# Power.net
KiCad netlist of a schematic drawn in Altium Designer
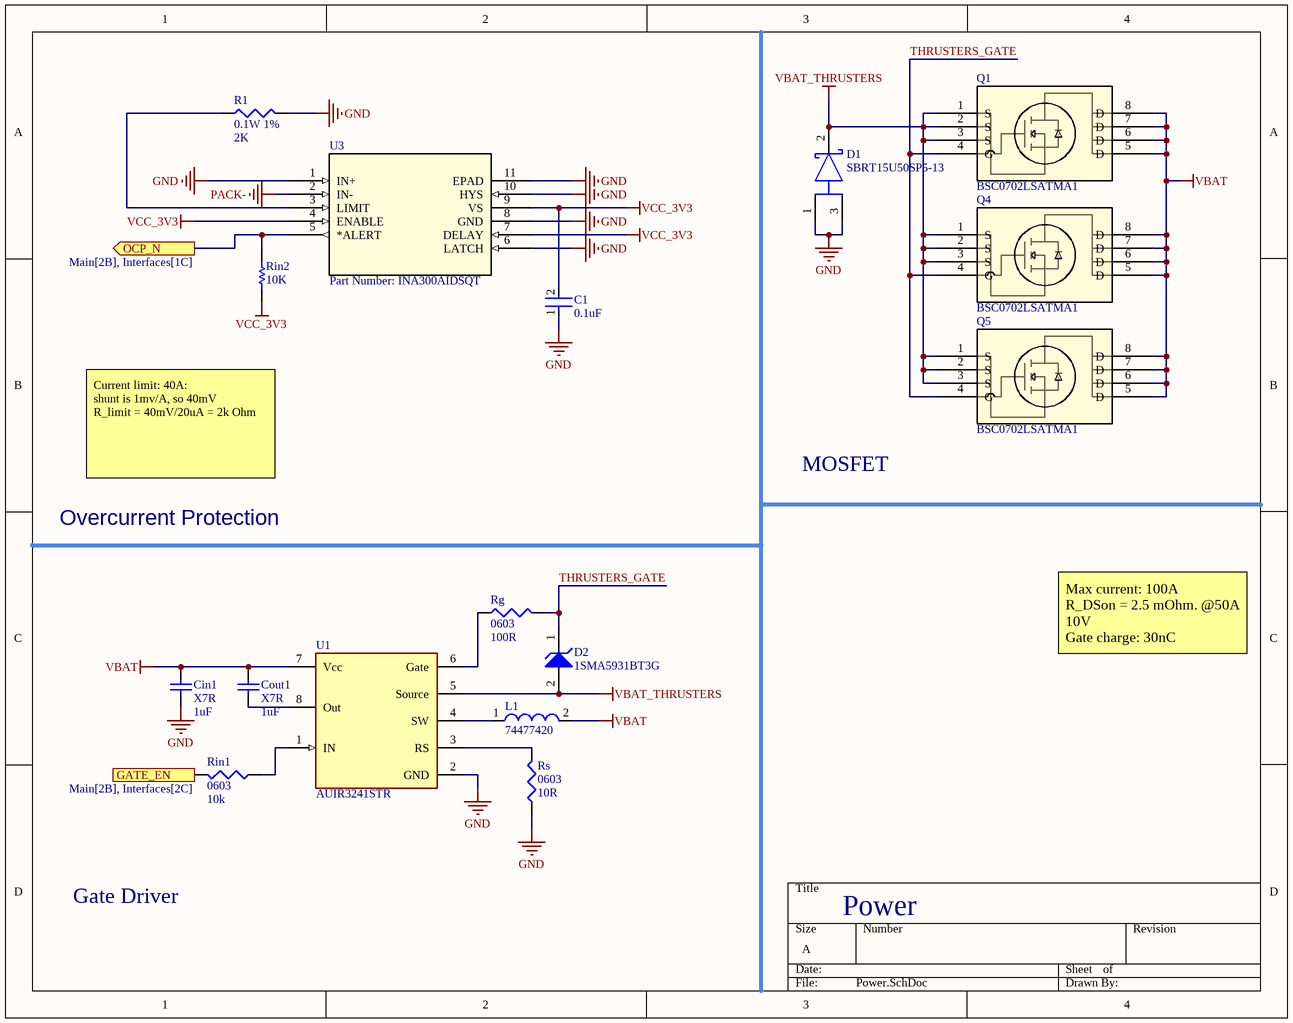
[diagram p0: Power.SchDoc]

(export (version "E")
  (design (tool "Eeschema 10.0.6"))
  (components
    (comp (ref "C1")
      (value "0.1uF")
      (footprint "FP-C0603C-CF-MFG")
      (description "CAP CER 0.1UF 10V X7R 0603")
      (fields (field (name "TOLERANCE") "0.1") (field (name "MANUFACTURER PART NUMBER") "C0603C104K8RACTU"))
      (libsource (lib "Altium Content Vault") (part "b4654b650e69147ec39a6b967a45e02"))
    )
    (comp (ref "Cin1")
      (value "X7R")
      (footprint "C0805")
      (description "Capacitor")
      (fields (field (name "ALTIUM_VALUE") "1uF") (field (name "PUBLISHER") "Altium Limited"))
      (libsource (lib "Miscellaneous Devices") (part "Cap"))
    )
    (comp (ref "Cout1")
      (value "X7R")
      (footprint "C0805")
      (description "Capacitor")
      (fields (field (name "ALTIUM_VALUE") "1uF") (field (name "PUBLISHER") "Altium Limited"))
      (libsource (lib "Miscellaneous Devices") (part "Cap"))
    )
    (comp (ref "D1")
      (value "SBRT15U50SP5-13")
      (footprint "FP-PowerDI5-MFG")
      (description "50V 15A Rectifier Schottky Diode")
      (fields
        (field (name "OCTOPART") "https://octopart.com/pds3200-13-diodes+inc.-332544")
        (field (name "MANUFACTURER") "Diodes Inc.")
      )
      (libsource (lib "Altium Content Vault") (part "0222f6c3f9f8f3c07decc49f824026a"))
    )
    (comp (ref "D2")
      (value "1SMA5931BT3G")
      (footprint "ONSC-SMA-2-403D-02_F_V")
      (description "1.5 W Zener Voltage Regulator, 2-Pin SMA, Pb-Free, Tape and Reel")
      (fields (field (name "MANUFACTURER") "On Semiconductor"))
      (libsource (lib "Altium Content Vault") (part "ONSC-K1A2-2"))
    )
    (comp (ref "L1")
      (value "74477420")
      (footprint "WE-PD2-M")
      (description "SMD Power Inductor WE-PD2, L = 100 µH")
      (libsource (lib "Altium Content Vault") (part "PAS-IND-INDUCTOR-2"))
    )
    (comp (ref "Q1")
      (value "BSC0702LSATMA1")
      (footprint "PG-TDSON-8-7")
      (description "No Description Available")
      (libsource (lib "TAUV-Lib") (part "BSC0702LSATMA1"))
    )
    (comp (ref "Q4")
      (value "BSC0702LSATMA1")
      (footprint "PG-TDSON-8-7")
      (description "No Description Available")
      (libsource (lib "TAUV-Lib") (part "BSC0702LSATMA1"))
    )
    (comp (ref "Q5")
      (value "BSC0702LSATMA1")
      (footprint "PG-TDSON-8-7")
      (description "No Description Available")
      (libsource (lib "TAUV-Lib") (part "BSC0702LSATMA1"))
    )
    (comp (ref "R1")
      (value "0.1W 1%")
      (footprint "J1-0603")
      (description "2k 0.1W 1%")
      (fields (field (name "ALTIUM_VALUE") "2K") (field (name "PUBLISHER") "Altium Limited"))
      (libsource (lib "Miscellaneous Devices") (part "Res3"))
    )
    (comp (ref "Rg")
      (value "0603")
      (footprint "J1-0603")
      (description "Resistor")
      (fields (field (name "ALTIUM_VALUE") "100R") (field (name "PUBLISHER") "Altium Limited"))
      (libsource (lib "Miscellaneous Devices") (part "Res3"))
    )
    (comp (ref "Rin1")
      (value "0603")
      (footprint "J1-0603")
      (description "Resistor")
      (fields (field (name "ALTIUM_VALUE") "10k") (field (name "PUBLISHER") "Altium Limited"))
      (libsource (lib "Miscellaneous Devices") (part "Res3"))
    )
    (comp (ref "Rin2")
      (value "10K")
      (footprint "RESC0603(1608)_N")
      (description "10K 0.1W 5% 0603 (1608 Metric)  SMD")
      (fields (field (name "TOLERANCE") "5 %") (field (name "POWER") "0.1 W"))
      (libsource (lib "Altium Content Vault") (part "RES"))
    )
    (comp (ref "Rs")
      (value "0603")
      (footprint "J1-0603")
      (description "Resistor")
      (fields (field (name "ALTIUM_VALUE") "10R") (field (name "PUBLISHER") "Altium Limited"))
      (libsource (lib "Miscellaneous Devices") (part "Res3"))
    )
    (comp (ref "U1")
      (value "AUIR3241STR")
      (footprint "FP-PG-DSO-8-MFG")
      (description "IC GATE DRVR HIGH-SIDE 8SO")
      (libsource (lib "Altium Content Vault") (part "34ae5cb6024c322bdcbf0313f74d293"))
    )
    (comp (ref "U3")
      (value "Part Number: INA300AIDSQT")
      (footprint "DSQ10_P9X1P5")
      (description "No Description Available")
      (fields
        (field (name "MANUFACTURER_PART_NUMBER") "INA300AIDSQT")
        (field (name "COPYRIGHT") "Copyright (C) 2018 Accelerated Designs. All rights reserved")
      )
      (libsource (lib "Tauv-Lib") (part "INA300AIDSQT"))
    )
  )
  (nets
    (net (code "1") (name "/GATE_EN") (class "Default")
      (node (ref "Rin1") (pin "2") (pinfunction "2_2") (pintype "passive"))
    )
    (net (code "2") (name "/OCP_N") (class "Default")
      (node (ref "Rin2") (pin "1") (pinfunction "1_1") (pintype "passive"))
      (node (ref "U3") (pin "5") (pinfunction "*ALERT_5") (pintype "output"))
    )
    (net (code "3") (name "/THRUSTERS_GATE") (class "Default")
      (node (ref "D2") (pin "1") (pinfunction "K_1") (pintype "passive"))
      (node (ref "Q1") (pin "4") (pinfunction "G_4") (pintype "passive"))
      (node (ref "Q4") (pin "4") (pinfunction "G_4") (pintype "passive"))
      (node (ref "Q5") (pin "4") (pinfunction "G_4") (pintype "passive"))
      (node (ref "Rg") (pin "2") (pinfunction "2_2") (pintype "passive"))
    )
    (net (code "4") (name "GND") (class "Default")
      (node (ref "C1") (pin "1") (pinfunction "1_1") (pintype "passive"))
      (node (ref "Cin1") (pin "1") (pinfunction "1_1") (pintype "passive"))
      (node (ref "D1") (pin "1") (pinfunction "A_1") (pintype "passive"))
      (node (ref "D1") (pin "3") (pinfunction "A_3") (pintype "passive"))
      (node (ref "R1") (pin "2") (pinfunction "2_2") (pintype "passive"))
      (node (ref "Rs") (pin "1") (pinfunction "1_1") (pintype "passive"))
      (node (ref "U1") (pin "2") (pinfunction "GND_2") (pintype "power_in"))
      (node (ref "U3") (pin "1") (pinfunction "IN+_1") (pintype "input"))
      (node (ref "U3") (pin "10") (pinfunction "HYS_10") (pintype "input"))
      (node (ref "U3") (pin "11") (pinfunction "EPAD_11") (pintype "passive"))
      (node (ref "U3") (pin "6") (pinfunction "LATCH_6") (pintype "input"))
      (node (ref "U3") (pin "8") (pinfunction "GND_8") (pintype "power_in"))
    )
    (net (code "5") (name "Net-(U1-Gate)") (class "Default")
      (node (ref "Rg") (pin "1") (pinfunction "1_1") (pintype "passive"))
      (node (ref "U1") (pin "6") (pinfunction "Gate_6") (pintype "passive"))
    )
    (net (code "6") (name "Net-(U1-IN)") (class "Default")
      (node (ref "Rin1") (pin "1") (pinfunction "1_1") (pintype "passive"))
      (node (ref "U1") (pin "1") (pinfunction "IN_1") (pintype "input"))
    )
    (net (code "7") (name "Net-(U1-Out)") (class "Default")
      (node (ref "Cout1") (pin "1") (pinfunction "1_1") (pintype "passive"))
      (node (ref "U1") (pin "8") (pinfunction "Out_8") (pintype "passive"))
    )
    (net (code "8") (name "Net-(U1-RS)") (class "Default")
      (node (ref "Rs") (pin "2") (pinfunction "2_2") (pintype "passive"))
      (node (ref "U1") (pin "3") (pinfunction "RS_3") (pintype "passive"))
    )
    (net (code "9") (name "Net-(U1-SW)") (class "Default")
      (node (ref "L1") (pin "1") (pinfunction "1_1") (pintype "passive"))
      (node (ref "U1") (pin "4") (pinfunction "SW_4") (pintype "passive"))
    )
    (net (code "10") (name "Net-(U3-LIMIT)") (class "Default")
      (node (ref "R1") (pin "1") (pinfunction "1_1") (pintype "passive"))
      (node (ref "U3") (pin "3") (pinfunction "LIMIT_3") (pintype "input"))
    )
    (net (code "11") (name "PACK-") (class "Default")
      (node (ref "U3") (pin "2") (pinfunction "IN-_2") (pintype "input"))
    )
    (net (code "12") (name "VBAT") (class "Default")
      (node (ref "Cin1") (pin "2") (pinfunction "2_2") (pintype "passive"))
      (node (ref "Cout1") (pin "2") (pinfunction "2_2") (pintype "passive"))
      (node (ref "L1") (pin "2") (pinfunction "2_2") (pintype "passive"))
      (node (ref "Q1") (pin "5") (pinfunction "D_5") (pintype "passive"))
      (node (ref "Q1") (pin "6") (pinfunction "D_6") (pintype "passive"))
      (node (ref "Q1") (pin "7") (pinfunction "D_7") (pintype "passive"))
      (node (ref "Q1") (pin "8") (pinfunction "D_8") (pintype "passive"))
      (node (ref "Q4") (pin "5") (pinfunction "D_5") (pintype "passive"))
      (node (ref "Q4") (pin "6") (pinfunction "D_6") (pintype "passive"))
      (node (ref "Q4") (pin "7") (pinfunction "D_7") (pintype "passive"))
      (node (ref "Q4") (pin "8") (pinfunction "D_8") (pintype "passive"))
      (node (ref "Q5") (pin "5") (pinfunction "D_5") (pintype "passive"))
      (node (ref "Q5") (pin "6") (pinfunction "D_6") (pintype "passive"))
      (node (ref "Q5") (pin "7") (pinfunction "D_7") (pintype "passive"))
      (node (ref "Q5") (pin "8") (pinfunction "D_8") (pintype "passive"))
      (node (ref "U1") (pin "7") (pinfunction "Vcc_7") (pintype "power_in"))
    )
    (net (code "13") (name "VBAT_THRUSTERS") (class "Default")
      (node (ref "D1") (pin "2") (pinfunction "C_2") (pintype "passive"))
      (node (ref "D2") (pin "2") (pinfunction "A_2") (pintype "passive"))
      (node (ref "Q1") (pin "1") (pinfunction "S_1") (pintype "passive"))
      (node (ref "Q1") (pin "2") (pinfunction "S_2") (pintype "passive"))
      (node (ref "Q1") (pin "3") (pinfunction "S_3") (pintype "passive"))
      (node (ref "Q4") (pin "1") (pinfunction "S_1") (pintype "passive"))
      (node (ref "Q4") (pin "2") (pinfunction "S_2") (pintype "passive"))
      (node (ref "Q4") (pin "3") (pinfunction "S_3") (pintype "passive"))
      (node (ref "Q5") (pin "1") (pinfunction "S_1") (pintype "passive"))
      (node (ref "Q5") (pin "2") (pinfunction "S_2") (pintype "passive"))
      (node (ref "Q5") (pin "3") (pinfunction "S_3") (pintype "passive"))
      (node (ref "U1") (pin "5") (pinfunction "Source_5") (pintype "passive"))
    )
    (net (code "14") (name "VCC_3V3") (class "Default")
      (node (ref "C1") (pin "2") (pinfunction "2_2") (pintype "passive"))
      (node (ref "Rin2") (pin "2") (pinfunction "2_2") (pintype "passive"))
      (node (ref "U3") (pin "4") (pinfunction "ENABLE_4") (pintype "input"))
      (node (ref "U3") (pin "7") (pinfunction "DELAY_7") (pintype "input"))
      (node (ref "U3") (pin "9") (pinfunction "VS_9") (pintype "power_in"))
    )
  )
)
